# untitled.net
KiCad netlist of a schematic drawn in EAGLE
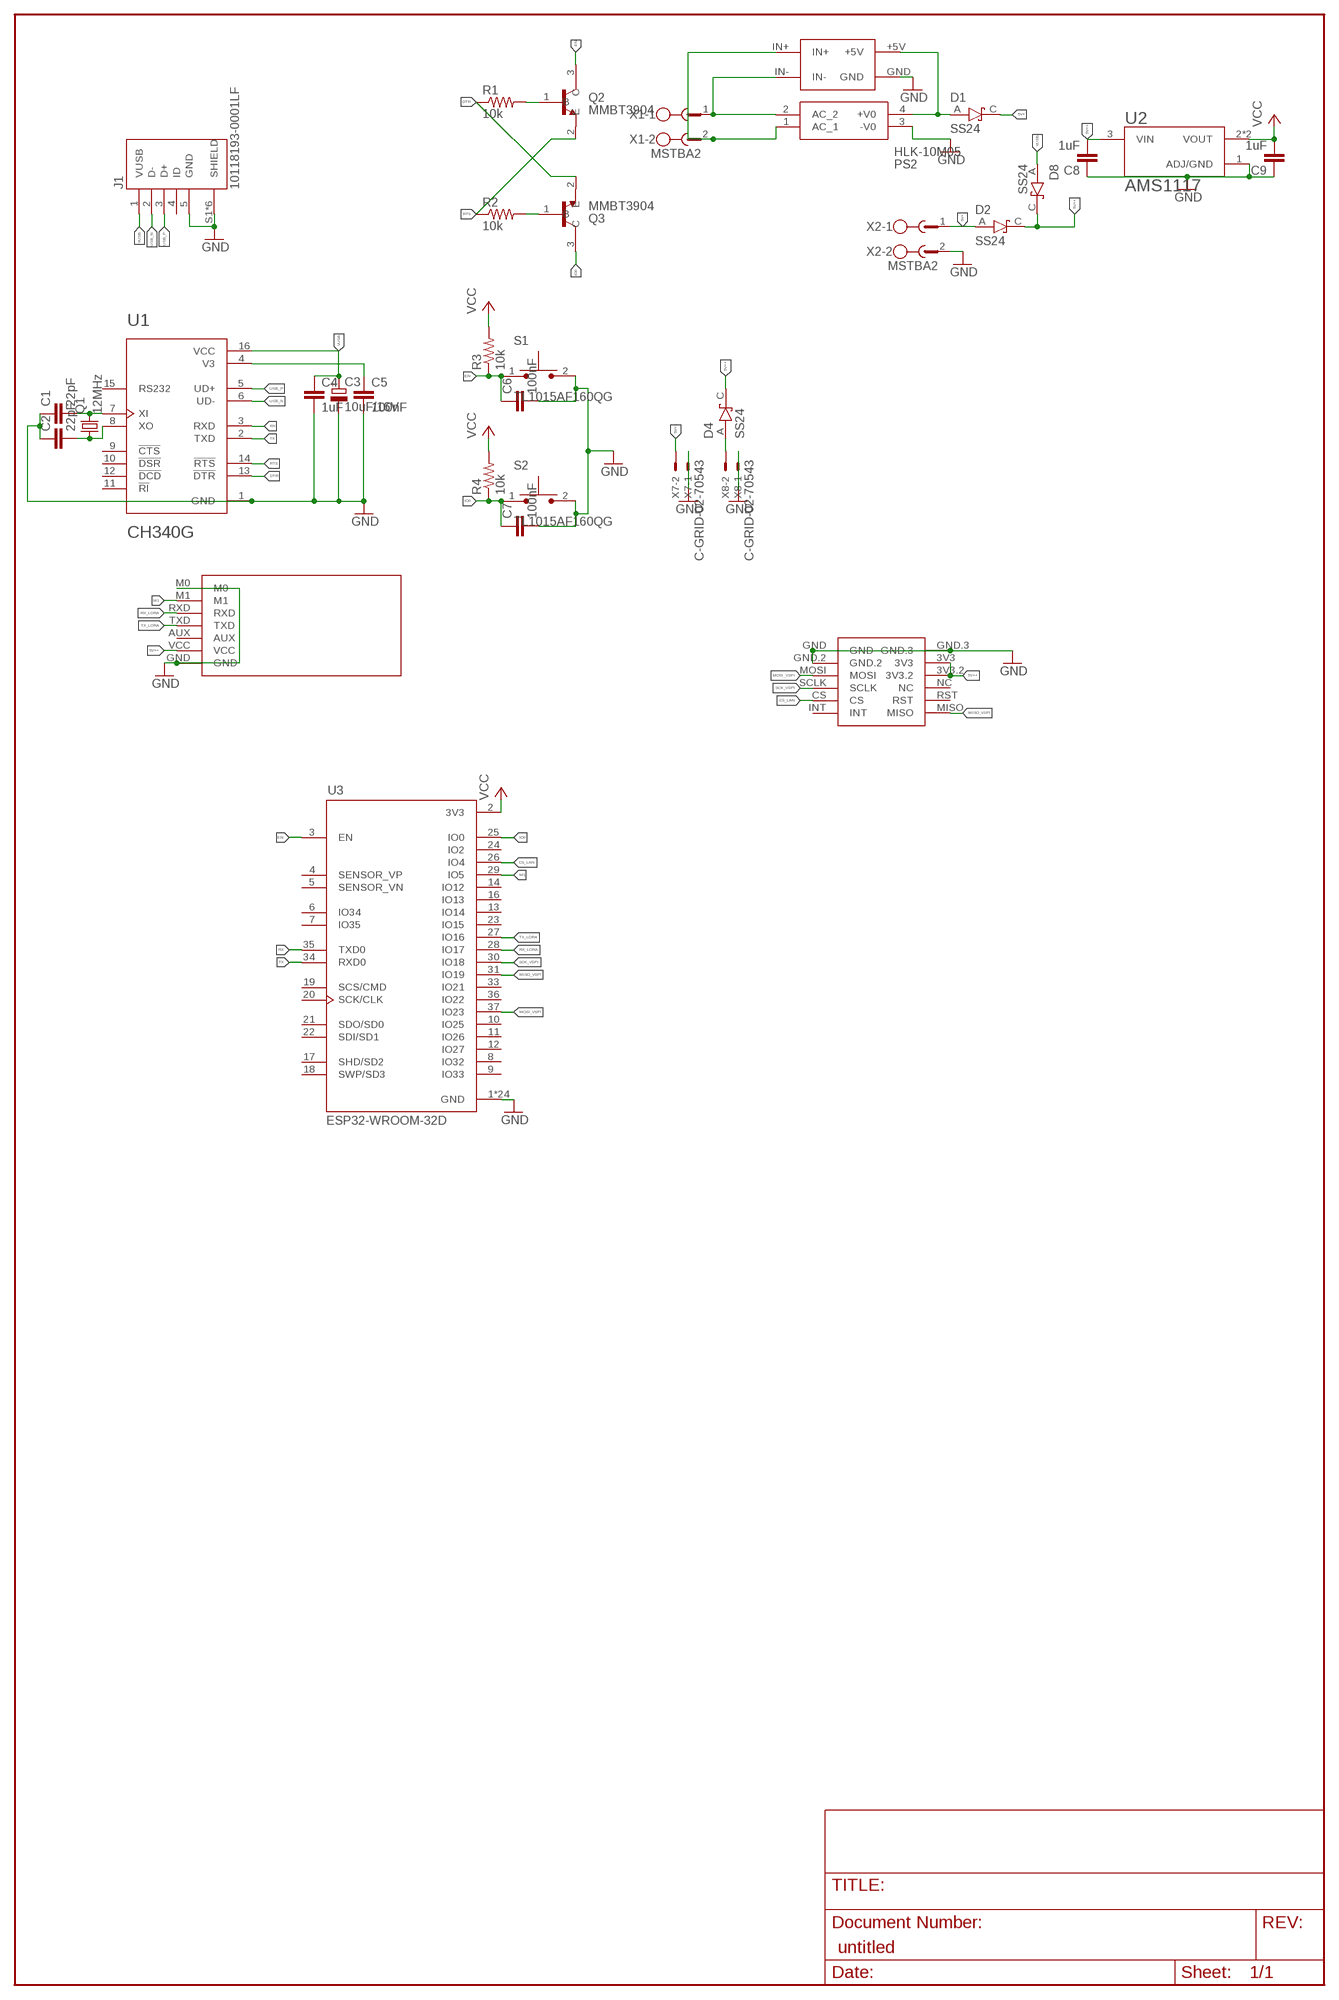
[diagram p0: schematic, sheet 1]

(export (version "E")
  (design (tool "Eeschema 10.0.6"))
  (components
    (comp (ref "C1")
      (value "22pF")
      (footprint "eagle-import:C0805K")
      (libsource (lib "eagle-import") (part "C-EUC0805K"))
    )
    (comp (ref "C2")
      (value "22pF")
      (footprint "eagle-import:C0805K")
      (libsource (lib "eagle-import") (part "C-EUC0805K"))
    )
    (comp (ref "C3")
      (value "10uF/16V")
      (footprint "eagle-import:153CLV-0505")
      (libsource (lib "eagle-import") (part "CPOL-EU153CLV-0505"))
    )
    (comp (ref "C4")
      (value "1uF")
      (footprint "eagle-import:C0805K")
      (libsource (lib "eagle-import") (part "C-EUC0805K"))
    )
    (comp (ref "C5")
      (value "100nF")
      (footprint "eagle-import:C0805K")
      (libsource (lib "eagle-import") (part "C-EUC0805K"))
    )
    (comp (ref "C6")
      (value "100nF")
      (footprint "eagle-import:C0805K")
      (libsource (lib "eagle-import") (part "C-EUC0805K"))
    )
    (comp (ref "C7")
      (value "100nF")
      (footprint "eagle-import:C0805K")
      (libsource (lib "eagle-import") (part "C-EUC0805K"))
    )
    (comp (ref "C8")
      (value "1uF")
      (footprint "eagle-import:C0805K")
      (libsource (lib "eagle-import") (part "C-EUC0805K"))
    )
    (comp (ref "C9")
      (value "1uF")
      (footprint "eagle-import:C0805K")
      (libsource (lib "eagle-import") (part "C-EUC0805K"))
    )
    (comp (ref "D1")
      (value "SS24")
      (footprint "eagle-import:DIOM5336X265N")
      (fields (field (name "MF") "ON Semiconductor"))
      (libsource (lib "eagle-import") (part "SS24"))
    )
    (comp (ref "D2")
      (value "SS24")
      (footprint "eagle-import:DIOM5336X265N")
      (fields (field (name "MF") "ON Semiconductor"))
      (libsource (lib "eagle-import") (part "SS24"))
    )
    (comp (ref "D4")
      (value "SS24")
      (footprint "eagle-import:DIOM5336X265N")
      (fields (field (name "MF") "ON Semiconductor"))
      (libsource (lib "eagle-import") (part "SS24"))
    )
    (comp (ref "D8")
      (value "SS24")
      (footprint "eagle-import:DIOM5336X265N")
      (fields (field (name "MF") "ON Semiconductor"))
      (libsource (lib "eagle-import") (part "SS24"))
    )
    (comp (ref "EBYTEE220-900T22D1")
      (value "EBYTEE220-900T22D")
      (footprint "eagle-import:EBYTEE220-900T22D")
      (libsource (lib "eagle-import") (part "EBYTEE220-900T22D"))
    )
    (comp (ref "J1")
      (value "10118193-0001LF")
      (footprint "eagle-import:FCI_10118193-0001LF")
      (fields (field (name "MF") "FCI"))
      (libsource (lib "eagle-import") (part "10118193-0001LF"))
    )
    (comp (ref "PS2")
      (value "HLK-10M05")
      (footprint "eagle-import:HLK10M05")
      (fields (field (name "MF") "Hi-link"))
      (libsource (lib "eagle-import") (part "HLK-10M05"))
    )
    (comp (ref "Q1")
      (value "12MHz")
      (footprint "eagle-import:SM49")
      (libsource (lib "eagle-import") (part "CRYSTALSM49"))
    )
    (comp (ref "Q2")
      (value "MMBT3904")
      (footprint "eagle-import:SOT95P240X120-3N")
      (fields (field (name "MF") "ON Semiconductor"))
      (libsource (lib "eagle-import") (part "MMBT3904"))
    )
    (comp (ref "Q3")
      (value "MMBT3904")
      (footprint "eagle-import:SOT95P240X120-3N")
      (fields (field (name "MF") "ON Semiconductor"))
      (libsource (lib "eagle-import") (part "MMBT3904"))
    )
    (comp (ref "R1")
      (value "10k")
      (footprint "eagle-import:M0805")
      (libsource (lib "eagle-import") (part "R-US_M0805"))
    )
    (comp (ref "R2")
      (value "10k")
      (footprint "eagle-import:M0805")
      (libsource (lib "eagle-import") (part "R-US_M0805"))
    )
    (comp (ref "R3")
      (value "10k")
      (footprint "eagle-import:M0805")
      (libsource (lib "eagle-import") (part "R-US_M0805"))
    )
    (comp (ref "R4")
      (value "10k")
      (footprint "eagle-import:M0805")
      (libsource (lib "eagle-import") (part "R-US_M0805"))
    )
    (comp (ref "S1")
      (value "TL1015AF160QG")
      (footprint "eagle-import:SW_TL1015AF160QG")
      (fields (field (name "MF") "E-Switch"))
      (libsource (lib "eagle-import") (part "TL1015AF160QG"))
    )
    (comp (ref "S2")
      (value "TL1015AF160QG")
      (footprint "eagle-import:SW_TL1015AF160QG")
      (fields (field (name "MF") "E-Switch"))
      (libsource (lib "eagle-import") (part "TL1015AF160QG"))
    )
    (comp (ref "SUPER-STEPDOWN1")
      (value "SUPER-STEPDOWN")
      (footprint "eagle-import:SUPER-STEPDOWN")
      (libsource (lib "eagle-import") (part "SUPER-STEPDOWN"))
    )
    (comp (ref "U$1")
      (value "MINI_W5500")
      (footprint "eagle-import:MINI_W5500")
      (libsource (lib "eagle-import") (part "MINI_W5500"))
    )
    (comp (ref "U1")
      (value "CH340G")
      (footprint "eagle-import:SOIC127P600X180-16N")
      (fields (field (name "MF") "WCH") (field (name "MP") "Ch340G"))
      (libsource (lib "eagle-import") (part "CH340G"))
    )
    (comp (ref "U2")
      (value "AMS1117")
      (footprint "eagle-import:SOT229P700X180-4N")
      (fields (field (name "MF") "Advanced Monolithic Systems"))
      (libsource (lib "eagle-import") (part "AMS1117"))
    )
    (comp (ref "U3")
      (value "ESP32-WROOM-32D")
      (footprint "eagle-import:MODULE_ESP32-WROOM-32D")
      (fields (field (name "MF") "Espressif Systems"))
      (libsource (lib "eagle-import") (part "ESP32-WROOM-32D"))
    )
    (comp (ref "X1")
      (value "MSTBA2")
      (footprint "eagle-import:MSTBA2")
      (fields (field (name "MF") "FARNELL") (field (name "MPN") "1757242"))
      (libsource (lib "eagle-import") (part "MSTBA2"))
    )
    (comp (ref "X2")
      (value "MSTBA2")
      (footprint "eagle-import:MSTBA2")
      (fields (field (name "MF") "FARNELL") (field (name "MPN") "1757242"))
      (libsource (lib "eagle-import") (part "MSTBA2"))
    )
    (comp (ref "X7")
      (value "C-GRID-02-70543")
      (footprint "eagle-import:70543-02")
      (fields (field (name "MF") "MOLEX"))
      (libsource (lib "eagle-import") (part "C-GRID-02-70543"))
    )
    (comp (ref "X8")
      (value "C-GRID-02-70543")
      (footprint "eagle-import:70543-02")
      (fields (field (name "MF") "MOLEX"))
      (libsource (lib "eagle-import") (part "C-GRID-02-70543"))
    )
  )
  (nets
    (net (code "1") (name "5V+") (class "Default")
      (node (ref "D1") (pin "C") (pinfunction "K_C") (pintype "passive"))
      (node (ref "D2") (pin "A") (pinfunction "A_A") (pintype "passive"))
      (node (ref "X2") (pin "1") (pinfunction "1_1") (pintype "passive"))
      (node (ref "X7") (pin "2") (pinfunction "S_2") (pintype "passive"))
    )
    (net (code "2") (name "5V++") (class "Default")
      (node (ref "C8") (pin "2") (pinfunction "2_2") (pintype "passive"))
      (node (ref "D2") (pin "C") (pinfunction "K_C") (pintype "passive"))
      (node (ref "D4") (pin "C") (pinfunction "K_C") (pintype "passive"))
      (node (ref "D8") (pin "C") (pinfunction "K_C") (pintype "passive"))
      (node (ref "EBYTEE220-900T22D1") (pin "VCC") (pinfunction "VCC_VCC") (pintype "bidirectional"))
      (node (ref "U$1") (pin "3V3") (pinfunction "3V3_3V3") (pintype "bidirectional"))
      (node (ref "U$1") (pin "3V3.2") (pinfunction "3V3.2_3V3.2") (pintype "bidirectional"))
      (node (ref "U2") (pin "3") (pinfunction "VIN_3") (pintype "input"))
    )
    (net (code "3") (name "CS_LAN") (class "Default")
      (node (ref "U$1") (pin "CS") (pinfunction "CS_CS") (pintype "bidirectional"))
      (node (ref "U3") (pin "26") (pinfunction "IO4_26") (pintype "bidirectional"))
    )
    (net (code "4") (name "DTR") (class "Default")
      (node (ref "Q3") (pin "2") (pinfunction "E_2") (pintype "passive"))
      (node (ref "R1") (pin "1") (pinfunction "1_1") (pintype "passive"))
      (node (ref "U1") (pin "13") (pinfunction "~{DTR}_13") (pintype "output"))
    )
    (net (code "5") (name "EN") (class "Default")
      (node (ref "C6") (pin "1") (pinfunction "1_1") (pintype "passive"))
      (node (ref "Q2") (pin "3") (pinfunction "C_3") (pintype "passive"))
      (node (ref "R3") (pin "1") (pinfunction "1_1") (pintype "passive"))
      (node (ref "S1") (pin "1") (pinfunction "1_1") (pintype "passive"))
      (node (ref "U3") (pin "3") (pinfunction "EN_3") (pintype "input"))
    )
    (net (code "6") (name "GND") (class "Default")
      (node (ref "C1") (pin "1") (pinfunction "1_1") (pintype "passive"))
      (node (ref "C2") (pin "1") (pinfunction "1_1") (pintype "passive"))
      (node (ref "C3") (pin "-") (pinfunction "-_-") (pintype "passive"))
      (node (ref "C4") (pin "2") (pinfunction "2_2") (pintype "passive"))
      (node (ref "C5") (pin "2") (pinfunction "2_2") (pintype "passive"))
      (node (ref "C6") (pin "2") (pinfunction "2_2") (pintype "passive"))
      (node (ref "C7") (pin "2") (pinfunction "2_2") (pintype "passive"))
      (node (ref "C8") (pin "1") (pinfunction "1_1") (pintype "passive"))
      (node (ref "C9") (pin "1") (pinfunction "1_1") (pintype "passive"))
      (node (ref "EBYTEE220-900T22D1") (pin "GND") (pinfunction "GND_GND") (pintype "bidirectional"))
      (node (ref "EBYTEE220-900T22D1") (pin "M0") (pinfunction "M0_M0") (pintype "bidirectional"))
      (node (ref "J1") (pin "5") (pinfunction "GND_5") (pintype "passive"))
      (node (ref "J1") (pin "S1") (pinfunction "SHIELD_S1") (pintype "passive"))
      (node (ref "J1") (pin "S2") (pinfunction "SHIELD_S2") (pintype "passive"))
      (node (ref "J1") (pin "S3") (pinfunction "SHIELD_S3") (pintype "passive"))
      (node (ref "J1") (pin "S4") (pinfunction "SHIELD_S4") (pintype "passive"))
      (node (ref "J1") (pin "S5") (pinfunction "SHIELD_S5") (pintype "passive"))
      (node (ref "J1") (pin "S6") (pinfunction "SHIELD_S6") (pintype "passive"))
      (node (ref "PS2") (pin "3") (pinfunction "-V0_3") (pintype "bidirectional"))
      (node (ref "S1") (pin "2") (pinfunction "2_2") (pintype "passive"))
      (node (ref "S2") (pin "2") (pinfunction "2_2") (pintype "passive"))
      (node (ref "SUPER-STEPDOWN1") (pin "GND") (pinfunction "GND_GND") (pintype "bidirectional"))
      (node (ref "U$1") (pin "GND") (pinfunction "GND_GND") (pintype "bidirectional"))
      (node (ref "U$1") (pin "GND.2") (pinfunction "GND.2_GND.2") (pintype "bidirectional"))
      (node (ref "U$1") (pin "GND.3") (pinfunction "GND.3_GND.3") (pintype "bidirectional"))
      (node (ref "U1") (pin "1") (pinfunction "GND_1") (pintype "power_in"))
      (node (ref "U2") (pin "1") (pinfunction "ADJ/GND_1") (pintype "power_in"))
      (node (ref "U3") (pin "1") (pinfunction "GND_1") (pintype "power_in"))
      (node (ref "U3") (pin "15") (pinfunction "GND_15") (pintype "power_in"))
      (node (ref "U3") (pin "38") (pinfunction "GND_38") (pintype "power_in"))
      (node (ref "U3") (pin "39_1") (pinfunction "GND_39_1") (pintype "power_in"))
      (node (ref "U3") (pin "39_10") (pinfunction "GND_39_10") (pintype "power_in"))
      (node (ref "U3") (pin "39_11") (pinfunction "GND_39_11") (pintype "power_in"))
      (node (ref "U3") (pin "39_12") (pinfunction "GND_39_12") (pintype "power_in"))
      (node (ref "U3") (pin "39_13") (pinfunction "GND_39_13") (pintype "power_in"))
      (node (ref "U3") (pin "39_14") (pinfunction "GND_39_14") (pintype "power_in"))
      (node (ref "U3") (pin "39_15") (pinfunction "GND_39_15") (pintype "power_in"))
      (node (ref "U3") (pin "39_16") (pinfunction "GND_39_16") (pintype "power_in"))
      (node (ref "U3") (pin "39_17") (pinfunction "GND_39_17") (pintype "power_in"))
      (node (ref "U3") (pin "39_18") (pinfunction "GND_39_18") (pintype "power_in"))
      (node (ref "U3") (pin "39_19") (pinfunction "GND_39_19") (pintype "power_in"))
      (node (ref "U3") (pin "39_2") (pinfunction "GND_39_2") (pintype "power_in"))
      (node (ref "U3") (pin "39_20") (pinfunction "GND_39_20") (pintype "power_in"))
      (node (ref "U3") (pin "39_21") (pinfunction "GND_39_21") (pintype "power_in"))
      (node (ref "U3") (pin "39_3") (pinfunction "GND_39_3") (pintype "power_in"))
      (node (ref "U3") (pin "39_4") (pinfunction "GND_39_4") (pintype "power_in"))
      (node (ref "U3") (pin "39_5") (pinfunction "GND_39_5") (pintype "power_in"))
      (node (ref "U3") (pin "39_6") (pinfunction "GND_39_6") (pintype "power_in"))
      (node (ref "U3") (pin "39_7") (pinfunction "GND_39_7") (pintype "power_in"))
      (node (ref "U3") (pin "39_8") (pinfunction "GND_39_8") (pintype "power_in"))
      (node (ref "U3") (pin "39_9") (pinfunction "GND_39_9") (pintype "power_in"))
      (node (ref "X2") (pin "2") (pinfunction "1_2") (pintype "passive"))
      (node (ref "X7") (pin "1") (pinfunction "S_1") (pintype "passive"))
      (node (ref "X8") (pin "1") (pinfunction "S_1") (pintype "passive"))
    )
    (net (code "7") (name "IO0") (class "Default")
      (node (ref "C7") (pin "1") (pinfunction "1_1") (pintype "passive"))
      (node (ref "Q3") (pin "3") (pinfunction "C_3") (pintype "passive"))
      (node (ref "R4") (pin "1") (pinfunction "1_1") (pintype "passive"))
      (node (ref "S2") (pin "1") (pinfunction "1_1") (pintype "passive"))
      (node (ref "U3") (pin "25") (pinfunction "IO0_25") (pintype "bidirectional"))
    )
    (net (code "8") (name "M1") (class "Default")
      (node (ref "EBYTEE220-900T22D1") (pin "M1") (pinfunction "M1_M1") (pintype "bidirectional"))
      (node (ref "U3") (pin "29") (pinfunction "IO5_29") (pintype "bidirectional"))
    )
    (net (code "9") (name "MISO_VSPI") (class "Default")
      (node (ref "U$1") (pin "MISO") (pinfunction "MISO_MISO") (pintype "bidirectional"))
      (node (ref "U3") (pin "31") (pinfunction "IO19_31") (pintype "bidirectional"))
    )
    (net (code "10") (name "MOSI_VSPI") (class "Default")
      (node (ref "U$1") (pin "MOSI") (pinfunction "MOSI_MOSI") (pintype "bidirectional"))
      (node (ref "U3") (pin "37") (pinfunction "IO23_37") (pintype "bidirectional"))
    )
    (net (code "11") (name "Net-(PS2-+V0)") (class "Default")
      (node (ref "D1") (pin "A") (pinfunction "A_A") (pintype "passive"))
      (node (ref "PS2") (pin "4") (pinfunction "+V0_4") (pintype "bidirectional"))
      (node (ref "SUPER-STEPDOWN1") (pin "+5V") (pinfunction "+5V_+5V") (pintype "bidirectional"))
    )
    (net (code "12") (name "Net-(PS2-AC_1)") (class "Default")
      (node (ref "PS2") (pin "1") (pinfunction "AC_1_1") (pintype "bidirectional"))
      (node (ref "SUPER-STEPDOWN1") (pin "IN+") (pinfunction "IN+_IN+") (pintype "bidirectional"))
      (node (ref "X1") (pin "2") (pinfunction "1_2") (pintype "passive"))
    )
    (net (code "13") (name "Net-(PS2-AC_2)") (class "Default")
      (node (ref "PS2") (pin "2") (pinfunction "AC_2_2") (pintype "bidirectional"))
      (node (ref "SUPER-STEPDOWN1") (pin "IN-") (pinfunction "IN-_IN-") (pintype "bidirectional"))
      (node (ref "X1") (pin "1") (pinfunction "1_1") (pintype "passive"))
    )
    (net (code "14") (name "Net-(Q2-B)") (class "Default")
      (node (ref "Q2") (pin "1") (pinfunction "B_1") (pintype "passive"))
      (node (ref "R1") (pin "2") (pinfunction "2_2") (pintype "passive"))
    )
    (net (code "15") (name "Net-(Q3-B)") (class "Default")
      (node (ref "Q3") (pin "1") (pinfunction "B_1") (pintype "passive"))
      (node (ref "R2") (pin "2") (pinfunction "2_2") (pintype "passive"))
    )
    (net (code "16") (name "Net-(U1-V3)") (class "Default")
      (node (ref "C5") (pin "1") (pinfunction "1_1") (pintype "passive"))
      (node (ref "U1") (pin "4") (pinfunction "V3_4") (pintype "power_in"))
    )
    (net (code "17") (name "Net-(U1-XI)") (class "Default")
      (node (ref "C1") (pin "2") (pinfunction "2_2") (pintype "passive"))
      (node (ref "Q1") (pin "2") (pinfunction "2_2") (pintype "passive"))
      (node (ref "U1") (pin "7") (pinfunction "XI_7") (pintype "input"))
    )
    (net (code "18") (name "Net-(U1-XO)") (class "Default")
      (node (ref "C2") (pin "2") (pinfunction "2_2") (pintype "passive"))
      (node (ref "Q1") (pin "1") (pinfunction "1_1") (pintype "passive"))
      (node (ref "U1") (pin "8") (pinfunction "XO_8") (pintype "output"))
    )
    (net (code "19") (name "Net-(X8B-S)") (class "Default")
      (node (ref "D4") (pin "A") (pinfunction "A_A") (pintype "passive"))
      (node (ref "X8") (pin "2") (pinfunction "S_2") (pintype "passive"))
    )
    (net (code "20") (name "RTS") (class "Default")
      (node (ref "Q2") (pin "2") (pinfunction "E_2") (pintype "passive"))
      (node (ref "R2") (pin "1") (pinfunction "1_1") (pintype "passive"))
      (node (ref "U1") (pin "14") (pinfunction "~{RTS}_14") (pintype "output"))
    )
    (net (code "21") (name "RX") (class "Default")
      (node (ref "U1") (pin "3") (pinfunction "RXD_3") (pintype "input"))
      (node (ref "U3") (pin "35") (pinfunction "TXD0_35") (pintype "bidirectional"))
    )
    (net (code "22") (name "RX_LORA") (class "Default")
      (node (ref "EBYTEE220-900T22D1") (pin "RXD") (pinfunction "RXD_RXD") (pintype "bidirectional"))
      (node (ref "U3") (pin "28") (pinfunction "IO17_28") (pintype "bidirectional"))
    )
    (net (code "23") (name "SCK_VSPI") (class "Default")
      (node (ref "U$1") (pin "SCLK") (pinfunction "SCLK_SCLK") (pintype "bidirectional"))
      (node (ref "U3") (pin "30") (pinfunction "IO18_30") (pintype "bidirectional"))
    )
    (net (code "24") (name "TX") (class "Default")
      (node (ref "U1") (pin "2") (pinfunction "TXD_2") (pintype "output"))
      (node (ref "U3") (pin "34") (pinfunction "RXD0_34") (pintype "bidirectional"))
    )
    (net (code "25") (name "TX_LORA") (class "Default")
      (node (ref "EBYTEE220-900T22D1") (pin "TXD") (pinfunction "TXD_TXD") (pintype "bidirectional"))
      (node (ref "U3") (pin "27") (pinfunction "IO16_27") (pintype "bidirectional"))
    )
    (net (code "26") (name "USB_N") (class "Default")
      (node (ref "J1") (pin "2") (pinfunction "D-_2") (pintype "passive"))
      (node (ref "U1") (pin "6") (pinfunction "UD-_6") (pintype "bidirectional"))
    )
    (net (code "27") (name "USB_P") (class "Default")
      (node (ref "J1") (pin "3") (pinfunction "D+_3") (pintype "passive"))
      (node (ref "U1") (pin "5") (pinfunction "UD+_5") (pintype "bidirectional"))
    )
    (net (code "28") (name "VCC") (class "Default")
      (node (ref "C9") (pin "2") (pinfunction "2_2") (pintype "passive"))
      (node (ref "R3") (pin "2") (pinfunction "2_2") (pintype "passive"))
      (node (ref "R4") (pin "2") (pinfunction "2_2") (pintype "passive"))
      (node (ref "U2") (pin "2") (pinfunction "VOUT_2") (pintype "output"))
      (node (ref "U2") (pin "4") (pinfunction "VOUT_4") (pintype "output"))
      (node (ref "U3") (pin "2") (pinfunction "3V3_2") (pintype "power_in"))
    )
    (net (code "29") (name "VUSB") (class "Default")
      (node (ref "C3") (pin "+") (pinfunction "+_+") (pintype "passive"))
      (node (ref "C4") (pin "1") (pinfunction "1_1") (pintype "passive"))
      (node (ref "D8") (pin "A") (pinfunction "A_A") (pintype "passive"))
      (node (ref "J1") (pin "1") (pinfunction "VUSB_1") (pintype "passive"))
      (node (ref "U1") (pin "16") (pinfunction "VCC_16") (pintype "power_in"))
    )
    (net (code "30") (name "unconnected-(EBYTEE220-900T22D1-PadAUX)") (class "Default")
      (node (ref "EBYTEE220-900T22D1") (pin "AUX") (pinfunction "AUX_AUX") (pintype "bidirectional"))
    )
    (net (code "31") (name "unconnected-(J1-ID-Pad4)") (class "Default")
      (node (ref "J1") (pin "4") (pinfunction "ID_4") (pintype "passive"))
    )
    (net (code "32") (name "unconnected-(U$1-PadINT)") (class "Default")
      (node (ref "U$1") (pin "INT") (pinfunction "INT_INT") (pintype "bidirectional"))
    )
    (net (code "33") (name "unconnected-(U$1-PadNC)") (class "Default")
      (node (ref "U$1") (pin "NC") (pinfunction "NC_NC") (pintype "bidirectional"))
    )
    (net (code "34") (name "unconnected-(U$1-PadRST)") (class "Default")
      (node (ref "U$1") (pin "RST") (pinfunction "RST_RST") (pintype "bidirectional"))
    )
    (net (code "35") (name "unconnected-(U1-RS232-Pad15)") (class "Default")
      (node (ref "U1") (pin "15") (pinfunction "RS232_15") (pintype "input"))
    )
    (net (code "36") (name "unconnected-(U1-~{CTS}-Pad9)") (class "Default")
      (node (ref "U1") (pin "9") (pinfunction "~{CTS}_9") (pintype "input"))
    )
    (net (code "37") (name "unconnected-(U1-~{DCD}-Pad12)") (class "Default")
      (node (ref "U1") (pin "12") (pinfunction "~{DCD}_12") (pintype "input"))
    )
    (net (code "38") (name "unconnected-(U1-~{DSR}-Pad10)") (class "Default")
      (node (ref "U1") (pin "10") (pinfunction "~{DSR}_10") (pintype "input"))
    )
    (net (code "39") (name "unconnected-(U1-~{RI}-Pad11)") (class "Default")
      (node (ref "U1") (pin "11") (pinfunction "~{RI}_11") (pintype "input"))
    )
    (net (code "40") (name "unconnected-(U3-IO2-Pad24)") (class "Default")
      (node (ref "U3") (pin "24") (pinfunction "IO2_24") (pintype "bidirectional"))
    )
    (net (code "41") (name "unconnected-(U3-IO12-Pad14)") (class "Default")
      (node (ref "U3") (pin "14") (pinfunction "IO12_14") (pintype "bidirectional"))
    )
    (net (code "42") (name "unconnected-(U3-IO13-Pad16)") (class "Default")
      (node (ref "U3") (pin "16") (pinfunction "IO13_16") (pintype "bidirectional"))
    )
    (net (code "43") (name "unconnected-(U3-IO14-Pad13)") (class "Default")
      (node (ref "U3") (pin "13") (pinfunction "IO14_13") (pintype "bidirectional"))
    )
    (net (code "44") (name "unconnected-(U3-IO15-Pad23)") (class "Default")
      (node (ref "U3") (pin "23") (pinfunction "IO15_23") (pintype "bidirectional"))
    )
    (net (code "45") (name "unconnected-(U3-IO21-Pad33)") (class "Default")
      (node (ref "U3") (pin "33") (pinfunction "IO21_33") (pintype "bidirectional"))
    )
    (net (code "46") (name "unconnected-(U3-IO22-Pad36)") (class "Default")
      (node (ref "U3") (pin "36") (pinfunction "IO22_36") (pintype "bidirectional"))
    )
    (net (code "47") (name "unconnected-(U3-IO25-Pad10)") (class "Default")
      (node (ref "U3") (pin "10") (pinfunction "IO25_10") (pintype "bidirectional"))
    )
    (net (code "48") (name "unconnected-(U3-IO26-Pad11)") (class "Default")
      (node (ref "U3") (pin "11") (pinfunction "IO26_11") (pintype "bidirectional"))
    )
    (net (code "49") (name "unconnected-(U3-IO27-Pad12)") (class "Default")
      (node (ref "U3") (pin "12") (pinfunction "IO27_12") (pintype "bidirectional"))
    )
    (net (code "50") (name "unconnected-(U3-IO32-Pad8)") (class "Default")
      (node (ref "U3") (pin "8") (pinfunction "IO32_8") (pintype "bidirectional"))
    )
    (net (code "51") (name "unconnected-(U3-IO33-Pad9)") (class "Default")
      (node (ref "U3") (pin "9") (pinfunction "IO33_9") (pintype "bidirectional"))
    )
    (net (code "52") (name "unconnected-(U3-IO34-Pad6)") (class "Default")
      (node (ref "U3") (pin "6") (pinfunction "IO34_6") (pintype "input"))
    )
    (net (code "53") (name "unconnected-(U3-IO35-Pad7)") (class "Default")
      (node (ref "U3") (pin "7") (pinfunction "IO35_7") (pintype "input"))
    )
    (net (code "54") (name "unconnected-(U3-SCK{slash}CLK-Pad20)") (class "Default")
      (node (ref "U3") (pin "20") (pinfunction "SCK/CLK_20") (pintype "bidirectional"))
    )
    (net (code "55") (name "unconnected-(U3-SCS{slash}CMD-Pad19)") (class "Default")
      (node (ref "U3") (pin "19") (pinfunction "SCS/CMD_19") (pintype "bidirectional"))
    )
    (net (code "56") (name "unconnected-(U3-SDI{slash}SD1-Pad22)") (class "Default")
      (node (ref "U3") (pin "22") (pinfunction "SDI/SD1_22") (pintype "bidirectional"))
    )
    (net (code "57") (name "unconnected-(U3-SDO{slash}SD0-Pad21)") (class "Default")
      (node (ref "U3") (pin "21") (pinfunction "SDO/SD0_21") (pintype "bidirectional"))
    )
    (net (code "58") (name "unconnected-(U3-SENSOR_VN-Pad5)") (class "Default")
      (node (ref "U3") (pin "5") (pinfunction "SENSOR_VN_5") (pintype "input"))
    )
    (net (code "59") (name "unconnected-(U3-SENSOR_VP-Pad4)") (class "Default")
      (node (ref "U3") (pin "4") (pinfunction "SENSOR_VP_4") (pintype "input"))
    )
    (net (code "60") (name "unconnected-(U3-SHD{slash}SD2-Pad17)") (class "Default")
      (node (ref "U3") (pin "17") (pinfunction "SHD/SD2_17") (pintype "bidirectional"))
    )
    (net (code "61") (name "unconnected-(U3-SWP{slash}SD3-Pad18)") (class "Default")
      (node (ref "U3") (pin "18") (pinfunction "SWP/SD3_18") (pintype "bidirectional"))
    )
  )
)
